# current-sensor.net
KiCad netlist of a schematic drawn in EAGLE
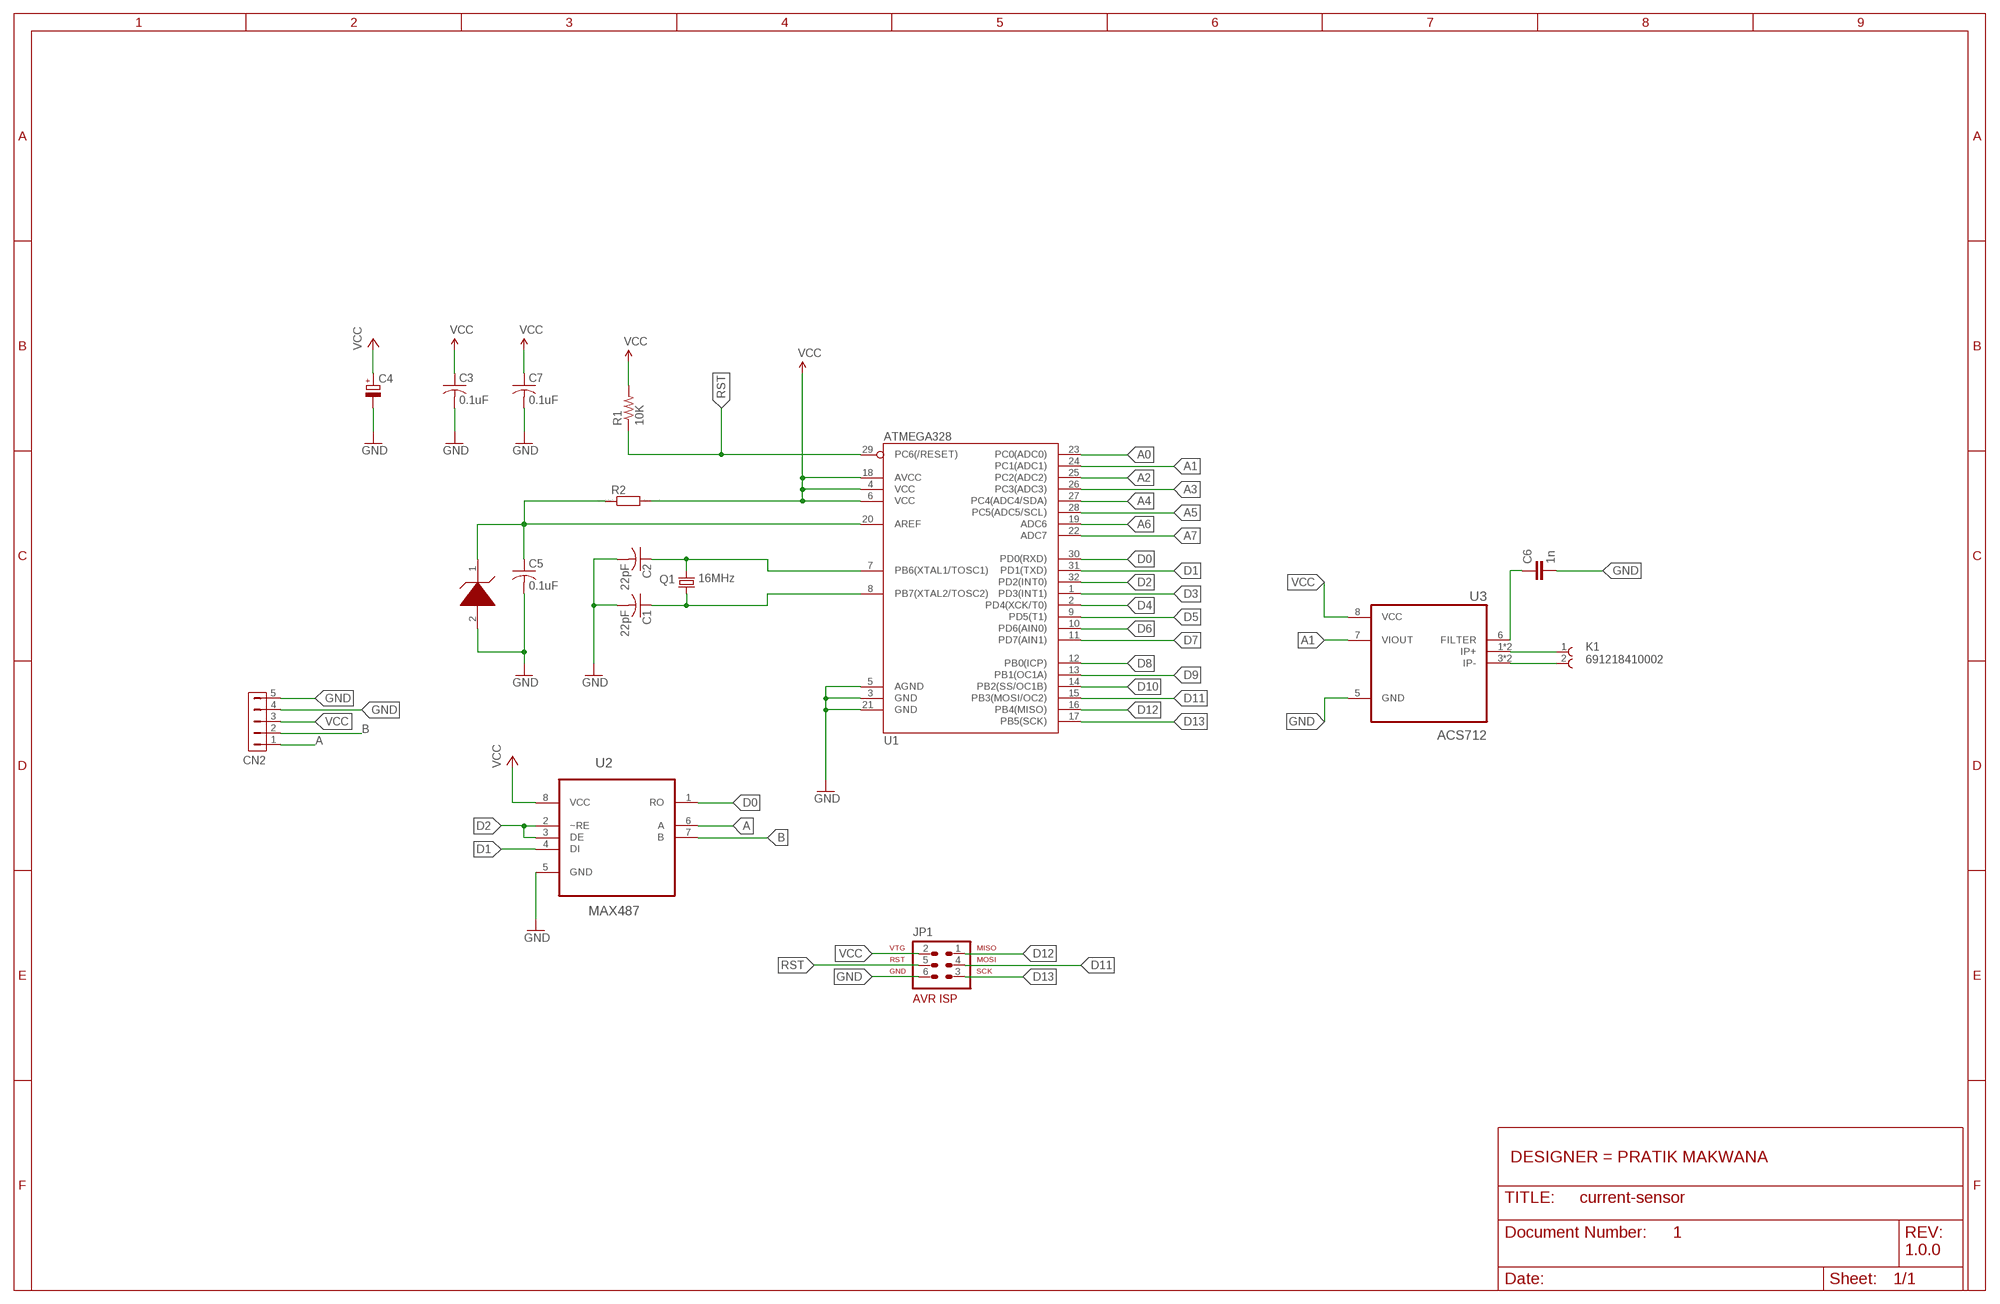
[diagram p0: schematic, sheet 1]

(export (version "E")
  (design (tool "Eeschema 10.0.6"))
  (components
    (comp (ref "C1")
      (value "22pF")
      (footprint "eagle-import:C1206")
      (libsource (lib "eagle-import") (part "C-USC1206"))
    )
    (comp (ref "C2")
      (value "22pF")
      (footprint "eagle-import:C1206")
      (libsource (lib "eagle-import") (part "C-USC1206"))
    )
    (comp (ref "C3")
      (value "0.1uF")
      (footprint "eagle-import:C0805")
      (libsource (lib "eagle-import") (part "C-USC0805"))
    )
    (comp (ref "C4")
      (value "CPOL-EUSANYO_SMD_C6")
      (footprint "eagle-import:SANYO-OSCON_SMD_C6")
      (libsource (lib "eagle-import") (part "CPOL-EUSANYO_SMD_C6"))
    )
    (comp (ref "C5")
      (value "0.1uF")
      (footprint "eagle-import:C0805")
      (libsource (lib "eagle-import") (part "C-USC0805"))
    )
    (comp (ref "C6")
      (value "1n")
      (footprint "eagle-import:C1206")
      (libsource (lib "eagle-import") (part "C-EUC1206"))
    )
    (comp (ref "C7")
      (value "0.1uF")
      (footprint "eagle-import:C0805")
      (libsource (lib "eagle-import") (part "C-USC0805"))
    )
    (comp (ref "CN2")
      (value "HDR-1X5-SIP-100")
      (footprint "eagle-import:SIP-100-5V")
      (libsource (lib "eagle-import") (part "HDR-1X5-SIP-100"))
    )
    (comp (ref "JP1")
      (value "AVR-ISP-6")
      (footprint "eagle-import:AVR-ISP-6")
      (libsource (lib "eagle-import") (part "AVR-ISP-6"))
    )
    (comp (ref "K1")
      (value "691218410002")
      (footprint "eagle-import:691218410002")
      (libsource (lib "eagle-import") (part "691218410002"))
    )
    (comp (ref "Q1")
      (value "16MHz")
      (footprint "eagle-import:HC49_S")
      (libsource (lib "eagle-import") (part "CRYTALHC49S"))
    )
    (comp (ref "R1")
      (value "10K")
      (footprint "eagle-import:R1206")
      (libsource (lib "eagle-import") (part "R-US_R1206"))
    )
    (comp (ref "R2")
      (value "RR1206")
      (footprint "eagle-import:R1206")
      (libsource (lib "eagle-import") (part "RR1206"))
    )
    (comp (ref "U$1")
      (value "LM4040")
      (footprint "eagle-import:SOT23")
      (libsource (lib "eagle-import") (part "LM4040"))
    )
    (comp (ref "U1")
      (value "ATMEGA328")
      (footprint "eagle-import:TQFP32-08")
      (libsource (lib "eagle-import") (part "ATMEGA328"))
    )
    (comp (ref "U2")
      (value "MAX487")
      (footprint "eagle-import:SOIC127P600X175-8N")
      (fields (field (name "MF") "Maxim Integrated") (field (name "MP") "MAX487ESA+TCBX"))
      (libsource (lib "eagle-import") (part "MAX487ESA+TCBX"))
    )
    (comp (ref "U3")
      (value "ACS712")
      (footprint "eagle-import:SOIC127P600X175-8N")
      (fields (field (name "MF") "Allegro") (field (name "MP") "ACS712ELCTR-20A-T"))
      (libsource (lib "eagle-import") (part "ACS712ELCTR-20A-T"))
    )
  )
  (nets
    (net (code "1") (name "A") (class "Default")
      (node (ref "CN2") (pin "1") (pinfunction "1_1") (pintype "passive"))
      (node (ref "U2") (pin "6") (pinfunction "A_6") (pintype "bidirectional"))
    )
    (net (code "2") (name "A0") (class "Default")
      (node (ref "U1") (pin "23") (pinfunction "PC0(ADC0)_23") (pintype "bidirectional"))
    )
    (net (code "3") (name "A1") (class "Default")
      (node (ref "U1") (pin "24") (pinfunction "PC1(ADC1)_24") (pintype "bidirectional"))
      (node (ref "U3") (pin "7") (pinfunction "VIOUT_7") (pintype "output"))
    )
    (net (code "4") (name "A2") (class "Default")
      (node (ref "U1") (pin "25") (pinfunction "PC2(ADC2)_25") (pintype "bidirectional"))
    )
    (net (code "5") (name "A3") (class "Default")
      (node (ref "U1") (pin "26") (pinfunction "PC3(ADC3)_26") (pintype "bidirectional"))
    )
    (net (code "6") (name "A4") (class "Default")
      (node (ref "U1") (pin "27") (pinfunction "PC4(ADC4/SDA)_27") (pintype "bidirectional"))
    )
    (net (code "7") (name "A5") (class "Default")
      (node (ref "U1") (pin "28") (pinfunction "PC5(ADC5/SCL)_28") (pintype "bidirectional"))
    )
    (net (code "8") (name "A6") (class "Default")
      (node (ref "U1") (pin "19") (pinfunction "ADC6_19") (pintype "bidirectional"))
    )
    (net (code "9") (name "A7") (class "Default")
      (node (ref "U1") (pin "22") (pinfunction "ADC7_22") (pintype "bidirectional"))
    )
    (net (code "10") (name "B") (class "Default")
      (node (ref "CN2") (pin "2") (pinfunction "2_2") (pintype "passive"))
      (node (ref "U2") (pin "7") (pinfunction "B_7") (pintype "bidirectional"))
    )
    (net (code "11") (name "D0") (class "Default")
      (node (ref "U1") (pin "30") (pinfunction "PD0(RXD)_30") (pintype "bidirectional"))
      (node (ref "U2") (pin "1") (pinfunction "RO_1") (pintype "output"))
    )
    (net (code "12") (name "D1") (class "Default")
      (node (ref "U1") (pin "31") (pinfunction "PD1(TXD)_31") (pintype "bidirectional"))
      (node (ref "U2") (pin "4") (pinfunction "DI_4") (pintype "input"))
    )
    (net (code "13") (name "D2") (class "Default")
      (node (ref "U1") (pin "32") (pinfunction "PD2(INT0)_32") (pintype "bidirectional"))
      (node (ref "U2") (pin "2") (pinfunction "~{RE}_2") (pintype "input"))
      (node (ref "U2") (pin "3") (pinfunction "DE_3") (pintype "input"))
    )
    (net (code "14") (name "D3") (class "Default")
      (node (ref "U1") (pin "1") (pinfunction "PD3(INT1)_1") (pintype "bidirectional"))
    )
    (net (code "15") (name "D4") (class "Default")
      (node (ref "U1") (pin "2") (pinfunction "PD4(XCK/T0)_2") (pintype "bidirectional"))
    )
    (net (code "16") (name "D5") (class "Default")
      (node (ref "U1") (pin "9") (pinfunction "PD5(T1)_9") (pintype "bidirectional"))
    )
    (net (code "17") (name "D6") (class "Default")
      (node (ref "U1") (pin "10") (pinfunction "PD6(AIN0)_10") (pintype "bidirectional"))
    )
    (net (code "18") (name "D7") (class "Default")
      (node (ref "U1") (pin "11") (pinfunction "PD7(AIN1)_11") (pintype "bidirectional"))
    )
    (net (code "19") (name "D8") (class "Default")
      (node (ref "U1") (pin "12") (pinfunction "PB0(ICP)_12") (pintype "bidirectional"))
    )
    (net (code "20") (name "D9") (class "Default")
      (node (ref "U1") (pin "13") (pinfunction "PB1(OC1A)_13") (pintype "bidirectional"))
    )
    (net (code "21") (name "D10") (class "Default")
      (node (ref "U1") (pin "14") (pinfunction "PB2(SS/OC1B)_14") (pintype "bidirectional"))
    )
    (net (code "22") (name "D11") (class "Default")
      (node (ref "JP1") (pin "4") (pinfunction "4_4") (pintype "passive"))
      (node (ref "U1") (pin "15") (pinfunction "PB3(MOSI/OC2)_15") (pintype "bidirectional"))
    )
    (net (code "23") (name "D12") (class "Default")
      (node (ref "JP1") (pin "1") (pinfunction "1_1") (pintype "passive"))
      (node (ref "U1") (pin "16") (pinfunction "PB4(MISO)_16") (pintype "bidirectional"))
    )
    (net (code "24") (name "D13") (class "Default")
      (node (ref "JP1") (pin "3") (pinfunction "3_3") (pintype "passive"))
      (node (ref "U1") (pin "17") (pinfunction "PB5(SCK)_17") (pintype "bidirectional"))
    )
    (net (code "25") (name "GND") (class "Default")
      (node (ref "C1") (pin "2") (pinfunction "2_2") (pintype "passive"))
      (node (ref "C2") (pin "2") (pinfunction "2_2") (pintype "passive"))
      (node (ref "C3") (pin "2") (pinfunction "2_2") (pintype "passive"))
      (node (ref "C4") (pin "-") (pinfunction "-_-") (pintype "passive"))
      (node (ref "C5") (pin "2") (pinfunction "2_2") (pintype "passive"))
      (node (ref "C6") (pin "2") (pinfunction "2_2") (pintype "passive"))
      (node (ref "C7") (pin "2") (pinfunction "2_2") (pintype "passive"))
      (node (ref "CN2") (pin "4") (pinfunction "4_4") (pintype "passive"))
      (node (ref "CN2") (pin "5") (pinfunction "5_5") (pintype "passive"))
      (node (ref "JP1") (pin "6") (pinfunction "6_6") (pintype "passive"))
      (node (ref "U$1") (pin "2") (pinfunction "ANODE_2") (pintype "bidirectional"))
      (node (ref "U1") (pin "21") (pinfunction "GND_21") (pintype "bidirectional"))
      (node (ref "U1") (pin "3") (pinfunction "GND_3") (pintype "bidirectional"))
      (node (ref "U1") (pin "5") (pinfunction "AGND_5") (pintype "bidirectional"))
      (node (ref "U2") (pin "5") (pinfunction "GND_5") (pintype "passive"))
      (node (ref "U3") (pin "5") (pinfunction "GND_5") (pintype "power_in"))
    )
    (net (code "26") (name "Net-(K1-Pad1)") (class "Default")
      (node (ref "K1") (pin "1") (pinfunction "1_1") (pintype "passive"))
      (node (ref "U3") (pin "1") (pinfunction "IP+_1") (pintype "input"))
      (node (ref "U3") (pin "2") (pinfunction "IP+_2") (pintype "input"))
    )
    (net (code "27") (name "Net-(K1-Pad2)") (class "Default")
      (node (ref "K1") (pin "2") (pinfunction "2_2") (pintype "passive"))
      (node (ref "U3") (pin "3") (pinfunction "IP-_3") (pintype "input"))
      (node (ref "U3") (pin "4") (pinfunction "IP-_4") (pintype "input"))
    )
    (net (code "28") (name "Net-(U$1-CATHODE)") (class "Default")
      (node (ref "C5") (pin "1") (pinfunction "1_1") (pintype "passive"))
      (node (ref "R2") (pin "1") (pinfunction "1_1") (pintype "passive"))
      (node (ref "U$1") (pin "1") (pinfunction "CATHODE_1") (pintype "bidirectional"))
      (node (ref "U1") (pin "20") (pinfunction "AREF_20") (pintype "bidirectional"))
    )
    (net (code "29") (name "Net-(U1-PB6(XTAL1{slash}TOSC1))") (class "Default")
      (node (ref "C2") (pin "1") (pinfunction "1_1") (pintype "passive"))
      (node (ref "Q1") (pin "2") (pinfunction "2_2") (pintype "passive"))
      (node (ref "U1") (pin "7") (pinfunction "PB6(XTAL1/TOSC1)_7") (pintype "bidirectional"))
    )
    (net (code "30") (name "Net-(U1-PB7(XTAL2{slash}TOSC2))") (class "Default")
      (node (ref "C1") (pin "1") (pinfunction "1_1") (pintype "passive"))
      (node (ref "Q1") (pin "1") (pinfunction "1_1") (pintype "passive"))
      (node (ref "U1") (pin "8") (pinfunction "PB7(XTAL2/TOSC2)_8") (pintype "bidirectional"))
    )
    (net (code "31") (name "Net-(U3-FILTER)") (class "Default")
      (node (ref "C6") (pin "1") (pinfunction "1_1") (pintype "passive"))
      (node (ref "U3") (pin "6") (pinfunction "FILTER_6") (pintype "input"))
    )
    (net (code "32") (name "RST") (class "Default")
      (node (ref "JP1") (pin "5") (pinfunction "5_5") (pintype "passive"))
      (node (ref "R1") (pin "1") (pinfunction "1_1") (pintype "passive"))
      (node (ref "U1") (pin "29") (pinfunction "PC6(/RESET)_29") (pintype "bidirectional"))
    )
    (net (code "33") (name "VCC") (class "Default")
      (node (ref "C3") (pin "1") (pinfunction "1_1") (pintype "passive"))
      (node (ref "C4") (pin "+") (pinfunction "+_+") (pintype "passive"))
      (node (ref "C7") (pin "1") (pinfunction "1_1") (pintype "passive"))
      (node (ref "CN2") (pin "3") (pinfunction "3_3") (pintype "passive"))
      (node (ref "JP1") (pin "2") (pinfunction "2_2") (pintype "passive"))
      (node (ref "R1") (pin "2") (pinfunction "2_2") (pintype "passive"))
      (node (ref "R2") (pin "2") (pinfunction "2_2") (pintype "passive"))
      (node (ref "U1") (pin "18") (pinfunction "AVCC_18") (pintype "bidirectional"))
      (node (ref "U1") (pin "4") (pinfunction "VCC_4") (pintype "bidirectional"))
      (node (ref "U1") (pin "6") (pinfunction "VCC_6") (pintype "bidirectional"))
      (node (ref "U2") (pin "8") (pinfunction "VCC_8") (pintype "power_in"))
      (node (ref "U3") (pin "8") (pinfunction "VCC_8") (pintype "power_in"))
    )
  )
)
